# Kicker2018.net
KiCad netlist of a schematic drawn in Altium Designer
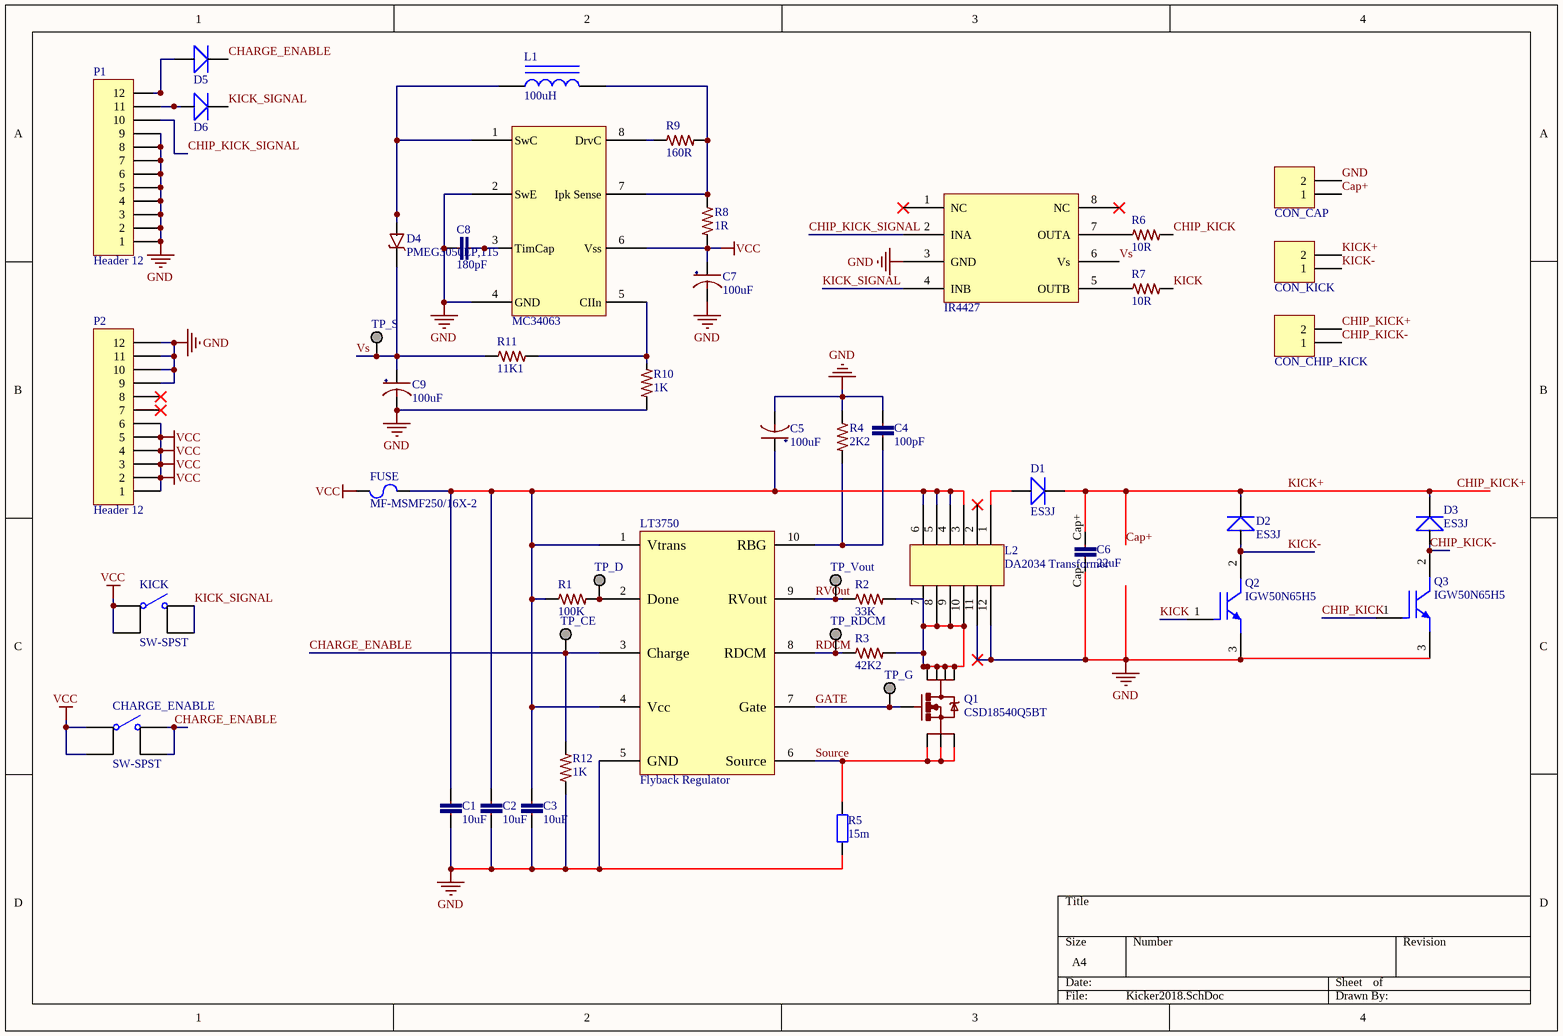
[diagram p0: Kicker2018.SchDoc]

(export (version "E")
  (design (tool "Eeschema 10.0.6"))
  (components
    (comp (ref "C1")
      (value "10uF")
      (footprint "CAPC0603(1608)55_L")
      (description "CAP CER 10UF 16V X5R 0603")
      (fields (field (name "PART NO") "EMK107BBJ106MA-T"))
      (libsource (lib "IMBEL") (part "CAPACITOR"))
    )
    (comp (ref "C2")
      (value "10uF")
      (footprint "CAPC0603(1608)55_L")
      (description "CAP CER 10UF 16V X5R 0603")
      (fields (field (name "PART NO") "EMK107BBJ106MA-T"))
      (libsource (lib "IMBEL") (part "CAPACITOR"))
    )
    (comp (ref "C3")
      (value "10uF")
      (footprint "CAPC0603(1608)55_L")
      (description "CAP CER 10UF 16V X5R 0603")
      (fields (field (name "PART NO") "EMK107BBJ106MA-T"))
      (libsource (lib "IMBEL") (part "CAPACITOR"))
    )
    (comp (ref "C4")
      (value "100pF")
      (footprint "CAPC0603(1608)55_L")
      (description "CAP CER 100PF 50V NP0 0603")
      (fields (field (name "PART NO") "GRM1885C1H101JA01D"))
      (libsource (lib "IMBEL") (part "CAPACITOR"))
    )
    (comp (ref "C5")
      (value "100uF")
      (footprint "7343-CAPPOL")
      (description "CAP TANT 100uF 25V 20% ESR = 30mOhm @ 100 kHz")
      (fields (field (name "PART NO") "T521X107M025ATE030"))
      (libsource (lib "IMBEL") (part "CT2917-100uF-1"))
    )
    (comp (ref "C6")
      (value "22uF")
      (footprint "CAP ALUM 22UF 250V")
      (libsource (lib "Schlib1") (part "CAP ALUM 22UF 250V"))
    )
    (comp (ref "C7")
      (value "100uF")
      (footprint "7343-CAPPOL")
      (description "CAP TANT 100uF 25V 20% ESR = 30mOhm @ 100 kHz")
      (fields (field (name "PART NO") "T521X107M025ATE030"))
      (libsource (lib "") (part "CT2917-100uF-1_1"))
    )
    (comp (ref "C8")
      (value "180pF")
      (footprint "0805-CAP")
      (description "CAP CER 180PF 50V NP0 0805")
      (fields (field (name "PART NO") "C0805C181K5GACTU"))
      (libsource (lib "IMBEL") (part "CC0805-180pF-2"))
    )
    (comp (ref "C9")
      (value "100uF")
      (footprint "7343-CAPPOL")
      (description "CAP TANT 100uF 25V 20% ESR = 30mOhm @ 100 kHz")
      (fields (field (name "PART NO") "T521X107M025ATE030"))
      (libsource (lib "") (part "CT2917-100uF-1_1"))
    )
    (comp (ref "CHARGE_ENABLE")
      (value "SW-SPST")
      (footprint "TACTILE SWITCH")
      (description "Single-Pole, Single-Throw Switch")
      (fields (field (name "PUBLISHER") "Altium Limited"))
      (libsource (lib "KickerSchlib") (part "SW-SPST"))
    )
    (comp (ref "CON_CAP")
      (value "OSTTA024163")
      (footprint "Term Block 2P")
      (description "2 Position Wire to Board Terminal Block Horizontal with Board 0.200\" (5.08mm) Through Hole")
      (libsource (lib "Schlib1") (part "Term Block 2P"))
    )
    (comp (ref "CON_CHIP_KICK")
      (value "OSTTA024163")
      (footprint "Term Block 2P")
      (description "2 Position Wire to Board Terminal Block Horizontal with Board 0.200\" (5.08mm) Through Hole")
      (libsource (lib "Schlib1") (part "Term Block 2P"))
    )
    (comp (ref "CON_KICK")
      (value "OSTTA024163")
      (footprint "Term Block 2P")
      (description "2 Position Wire to Board Terminal Block Horizontal with Board 0.200\" (5.08mm) Through Hole")
      (libsource (lib "Schlib1") (part "Term Block 2P"))
    )
    (comp (ref "D1") (value "ES3J") (footprint "Diode") (libsource (lib "KickerSchlib") (part "ES3J")))
    (comp (ref "D2") (value "ES3J") (footprint "Diode") (libsource (lib "KickerSchlib") (part "ES3J")))
    (comp (ref "D3") (value "ES3J") (footprint "Diode") (libsource (lib "KickerSchlib") (part "ES3J")))
    (comp (ref "D4")
      (value "PMEG3050EP,115")
      (footprint "PCBComponent")
      (description "DIODE SCHOTTKY 30V 5A SOD128")
      (libsource (lib "IMBEL") (part "PMEG3050EP,115-01.A.5"))
    )
    (comp (ref "D5")
      (value "BAS40 Diode")
      (footprint "DIODE SOD-523")
      (libsource (lib "KickerSchlib") (part "BAS40 Diode"))
    )
    (comp (ref "D6")
      (value "BAS40 Diode")
      (footprint "DIODE SOD-523")
      (libsource (lib "KickerSchlib") (part "BAS40 Diode"))
    )
    (comp (ref "FUSE")
      (value "MF-MSMF250/16X-2")
      (footprint "MF-MSMF250/16X-PCB")
      (description "PTC RESETTABLE")
      (libsource (lib "KickerSchlib") (part "MF-MSMF250/16X-2"))
    )
    (comp (ref "IR4427")
      (value "GATE DRIVER")
      (footprint "IR4427")
      (description "IC DRIVER DUAL LOW SIDE 8-SOIC")
      (libsource (lib "KickerSchlib") (part "IR4427"))
    )
    (comp (ref "KICK")
      (value "SW-SPST")
      (footprint "TACTILE SWITCH")
      (description "Single-Pole, Single-Throw Switch")
      (fields (field (name "PUBLISHER") "Altium Limited"))
      (libsource (lib "KickerSchlib") (part "SW-SPST"))
    )
    (comp (ref "L1")
      (value "100uH")
      (footprint "INDUCTOR")
      (description "Fixed Inductors 100uH 0.86A SMT")
      (libsource (lib "KickerSchlib") (part "Inductor"))
    )
    (comp (ref "L2")
      (value "DA2034 Transformer")
      (footprint "DA2034 Transformer")
      (libsource (lib "KickerSchlib") (part "DA2034 Transformer"))
    )
    (comp (ref "LT3750")
      (value "Flyback Regulator")
      (footprint "LT3750")
      (libsource (lib "KickerSchlib") (part "LT3750"))
    )
    (comp (ref "MC34063")
      (value "Switching Voltage Regulator")
      (footprint "DIP-8")
      (libsource (lib "KickerSchlib") (part "MC34063"))
    )
    (comp (ref "P1")
      (value "Header 12")
      (footprint "HDR1X12")
      (description "Header, 12-Pin")
      (fields (field (name "PUBLISHER") "Altium Limited"))
      (libsource (lib "Miscellaneous Connectors") (part "Header 12"))
    )
    (comp (ref "P2")
      (value "Header 12")
      (footprint "HDR1X12")
      (description "Header, 12-Pin")
      (fields (field (name "PUBLISHER") "Altium Limited"))
      (libsource (lib "Miscellaneous Connectors") (part "Header 12"))
    )
    (comp (ref "Q1")
      (value "CSD18540Q5BT")
      (footprint "PCBComponent")
      (description "MOSFET N-CH 60V 100A 8VSON")
      (libsource (lib "IMBEL") (part "MOSFET-NCHANNEL"))
    )
    (comp (ref "Q2")
      (value "IGW50N65H5")
      (footprint "INF-PG-TO247-3-44")
      (description "650 V IGBT High Speed Switching Series Fifth Generation, 80 A IC, PG-TO247-3-44, Tube, Green")
      (fields (field (name "MANUFACTURER") "Infineon"))
      (libsource (lib "KickerSchlib") (part "IGW50N65H5"))
    )
    (comp (ref "Q3")
      (value "IGW50N65H5")
      (footprint "INF-PG-TO247-3-44")
      (description "650 V IGBT High Speed Switching Series Fifth Generation, 80 A IC, PG-TO247-3-44, Tube, Green")
      (fields (field (name "MANUFACTURER") "Infineon"))
      (libsource (lib "KickerSchlib") (part "IGW50N65H5"))
    )
    (comp (ref "R1")
      (value "100K")
      (footprint "0402-RES-HD")
      (description "RES 100K OHM 1/10W 1% 0402 SMD 1")
      (fields (field (name "PART NO") "ERJ-2GEJ104X"))
      (libsource (lib "IMBEL") (part "RESISTOR"))
    )
    (comp (ref "R2")
      (value "33K")
      (footprint "0402-RES-HD")
      (description "RES 33K OHM 1/10W 1% 0402 SMD")
      (fields (field (name "PART NO") "ERJ-2RKF3302X"))
      (libsource (lib "IMBEL") (part "RESISTOR"))
    )
    (comp (ref "R3")
      (value "42K2")
      (footprint "0402-RES-HD")
      (description "RES 42.2K OHM 1/10W 1% 0402 SMD")
      (fields (field (name "PART NO") "ERJ-2RKF4222X"))
      (libsource (lib "Schlib1") (part "RESISTOR"))
    )
    (comp (ref "R4")
      (value "2K2")
      (footprint "0402-RES-HD")
      (description "RES 2.2K OHM 1/10W 1% 0402 SMD")
      (fields (field (name "PART NO") "ERJ-2RKF2201X"))
      (libsource (lib "IMBEL") (part "RESISTOR"))
    )
    (comp (ref "R5")
      (value "15m")
      (footprint "RES1206")
      (description "Resistor")
      (fields (field (name "PUBLISHER") "Altium Limited"))
      (libsource (lib "Schlib1") (part "Res2"))
    )
    (comp (ref "R6")
      (value "10R")
      (footprint "0402-RES-HD")
      (description "RES 10 OHM 1/10W 1% 0402 SMD")
      (fields (field (name "PART NO") "ERJ-2RKF10R0X"))
      (libsource (lib "IMBEL") (part "RESISTOR"))
    )
    (comp (ref "R7")
      (value "10R")
      (footprint "0402-RES-HD")
      (description "RES 10 OHM 1/10W 1% 0402 SMD")
      (fields (field (name "PART NO") "ERJ-2RKF10R0X"))
      (libsource (lib "IMBEL") (part "RESISTOR"))
    )
    (comp (ref "R8")
      (value "1R")
      (footprint "0805-RES")
      (description "RES SMD 1 OHM 1% 1/8W 0805")
      (fields (field (name "PART NO") "CRCW08051R00FKEA"))
      (libsource (lib "IMBEL") (part "R0805-1R-1%-1"))
    )
    (comp (ref "R9")
      (value "160R")
      (footprint "0805-RES")
      (description "RES 160 OHM 1/8W .5% 0805 SMD")
      (fields (field (name "PART NO") "ERA-6AED161V"))
      (libsource (lib "IMBEL") (part "R0805-160R-5"))
    )
    (comp (ref "R10")
      (value "1K")
      (footprint "0402-RES-HD")
      (description "RES 1K OHM 1/10W 1% 0402 SMD")
      (fields (field (name "PART NO") "ERJ-2RKF1001X"))
      (libsource (lib "IMBEL") (part "R0402-1K-A.9"))
    )
    (comp (ref "R11")
      (value "11K1")
      (footprint "0402-RES-HD")
      (description "RES 11.1 KOHM 1/16W 0.1% 0402 SMD")
      (fields (field (name "PART NO") "TNPW040211K1BEED"))
      (libsource (lib "IMBEL") (part "R0402-11K1-1"))
    )
    (comp (ref "R12")
      (value "1K")
      (footprint "0402-RES-HD")
      (description "RES 1K OHM 1/10W 1% 0402 SMD")
      (fields (field (name "PART NO") "ERJ-2RKF1001X"))
      (libsource (lib "IMBEL") (part "RESISTOR"))
    )
    (comp (ref "TP_CE")
      (value "~")
      (footprint "TP-PCB")
      (description "TESTPOINT")
      (libsource (lib "IMBEL") (part "TP-SCH"))
    )
    (comp (ref "TP_D")
      (value "~")
      (footprint "TP-PCB")
      (description "TESTPOINT")
      (libsource (lib "IMBEL") (part "TP-SCH"))
    )
    (comp (ref "TP_G")
      (value "~")
      (footprint "TP-PCB")
      (description "TESTPOINT")
      (libsource (lib "IMBEL") (part "TP-SCH"))
    )
    (comp (ref "TP_RDCM")
      (value "~")
      (footprint "TP-PCB")
      (description "TESTPOINT")
      (libsource (lib "IMBEL") (part "TP-SCH"))
    )
    (comp (ref "TP_S")
      (value "~")
      (footprint "TP-PCB")
      (description "TESTPOINT")
      (libsource (lib "IMBEL") (part "TP-SCH"))
    )
    (comp (ref "TP_Vout")
      (value "~")
      (footprint "TP-PCB")
      (description "TESTPOINT")
      (libsource (lib "IMBEL") (part "TP-SCH"))
    )
  )
  (nets
    (net (code "1") (name "/CHARGE_ENABLE") (class "Default")
      (node (ref "CHARGE_ENABLE") (pin "3") (pinfunction "3_3") (pintype "passive"))
      (node (ref "CHARGE_ENABLE") (pin "4") (pinfunction "4_4") (pintype "passive"))
      (node (ref "D5") (pin "2") (pinfunction "D-_2") (pintype "passive"))
      (node (ref "LT3750") (pin "3") (pinfunction "Charge_3") (pintype "passive"))
      (node (ref "R12") (pin "2") (pinfunction "2_2") (pintype "passive"))
      (node (ref "TP_CE") (pin "1") (pinfunction "1_1") (pintype "passive"))
    )
    (net (code "2") (name "/CHIP_KICK") (class "Default")
      (node (ref "Q3") (pin "1") (pinfunction "G_1") (pintype "passive"))
      (node (ref "R6") (pin "2") (pinfunction "2_2") (pintype "passive"))
    )
    (net (code "3") (name "/CHIP_KICK+") (class "Default")
      (node (ref "C6") (pin "Cap+") (pinfunction "Cap+_Cap+") (pintype "passive"))
      (node (ref "CON_CAP") (pin "1") (pinfunction "1_1") (pintype "passive"))
      (node (ref "CON_CHIP_KICK") (pin "2") (pinfunction "2_2") (pintype "passive"))
      (node (ref "CON_KICK") (pin "2") (pinfunction "2_2") (pintype "passive"))
      (node (ref "D1") (pin "D1+") (pinfunction "D1+_D1+") (pintype "passive"))
      (node (ref "D2") (pin "D1+") (pinfunction "D1+_D1+") (pintype "passive"))
      (node (ref "D3") (pin "D1+") (pinfunction "D1+_D1+") (pintype "passive"))
    )
    (net (code "4") (name "/CHIP_KICK-") (class "Default")
      (node (ref "CON_CHIP_KICK") (pin "1") (pinfunction "1_1") (pintype "passive"))
      (node (ref "D3") (pin "D1-") (pinfunction "D1-_D1-") (pintype "passive"))
      (node (ref "Q3") (pin "2") (pinfunction "C_2") (pintype "passive"))
    )
    (net (code "5") (name "/CHIP_KICK_SIGNAL") (class "Default")
      (node (ref "IR4427") (pin "2") (pinfunction "INA_2") (pintype "passive"))
      (node (ref "P1") (pin "10") (pinfunction "10_10") (pintype "passive"))
    )
    (net (code "6") (name "/GATE") (class "Default")
      (node (ref "LT3750") (pin "7") (pinfunction "Gate_7") (pintype "passive"))
      (node (ref "Q1") (pin "4") (pinfunction "G_4") (pintype "passive"))
      (node (ref "TP_G") (pin "1") (pinfunction "1_1") (pintype "passive"))
    )
    (net (code "7") (name "/KICK") (class "Default")
      (node (ref "Q2") (pin "1") (pinfunction "G_1") (pintype "passive"))
      (node (ref "R7") (pin "2") (pinfunction "2_2") (pintype "passive"))
    )
    (net (code "8") (name "/KICK-") (class "Default")
      (node (ref "CON_KICK") (pin "1") (pinfunction "1_1") (pintype "passive"))
      (node (ref "D2") (pin "D1-") (pinfunction "D1-_D1-") (pintype "passive"))
      (node (ref "Q2") (pin "2") (pinfunction "C_2") (pintype "passive"))
    )
    (net (code "9") (name "/KICK_SIGNAL") (class "Default")
      (node (ref "D6") (pin "2") (pinfunction "D-_2") (pintype "passive"))
      (node (ref "IR4427") (pin "4") (pinfunction "INB_4") (pintype "passive"))
      (node (ref "KICK") (pin "3") (pinfunction "3_3") (pintype "passive"))
      (node (ref "KICK") (pin "4") (pinfunction "4_4") (pintype "passive"))
    )
    (net (code "10") (name "/RDCM") (class "Default")
      (node (ref "LT3750") (pin "8") (pinfunction "RDCM_8") (pintype "passive"))
      (node (ref "R3") (pin "1") (pinfunction "1_1") (pintype "passive"))
      (node (ref "TP_RDCM") (pin "1") (pinfunction "1_1") (pintype "passive"))
    )
    (net (code "11") (name "/RVOut") (class "Default")
      (node (ref "LT3750") (pin "9") (pinfunction "RVout_9") (pintype "passive"))
      (node (ref "R2") (pin "1") (pinfunction "1_1") (pintype "passive"))
      (node (ref "TP_Vout") (pin "1") (pinfunction "1_1") (pintype "passive"))
    )
    (net (code "12") (name "/Source") (class "Default")
      (node (ref "LT3750") (pin "6") (pinfunction "Source_6") (pintype "passive"))
      (node (ref "Q1") (pin "1") (pinfunction "S_1") (pintype "passive"))
      (node (ref "Q1") (pin "2") (pinfunction "S_2") (pintype "passive"))
      (node (ref "Q1") (pin "3") (pinfunction "S_3") (pintype "passive"))
      (node (ref "R5") (pin "1") (pinfunction "1_1") (pintype "passive"))
    )
    (net (code "13") (name "/Vs") (class "Default")
      (node (ref "C9") (pin "1") (pinfunction "+_1") (pintype "passive"))
      (node (ref "D4") (pin "1") (pinfunction "C_1") (pintype "passive"))
      (node (ref "IR4427") (pin "6") (pinfunction "Vs_6") (pintype "passive"))
      (node (ref "R11") (pin "1") (pinfunction "1_1") (pintype "passive"))
      (node (ref "TP_S") (pin "1") (pinfunction "1_1") (pintype "passive"))
    )
    (net (code "14") (name "GND") (class "Default")
      (node (ref "C1") (pin "2") (pinfunction "2_2") (pintype "passive"))
      (node (ref "C2") (pin "2") (pinfunction "2_2") (pintype "passive"))
      (node (ref "C3") (pin "2") (pinfunction "2_2") (pintype "passive"))
      (node (ref "C4") (pin "1") (pinfunction "1_1") (pintype "passive"))
      (node (ref "C5") (pin "2") (pinfunction "-_2") (pintype "passive"))
      (node (ref "C6") (pin "Cap-") (pinfunction "Cap-_Cap-") (pintype "passive"))
      (node (ref "C7") (pin "2") (pinfunction "-_2") (pintype "passive"))
      (node (ref "C8") (pin "1") (pinfunction "1_1") (pintype "passive"))
      (node (ref "C9") (pin "2") (pinfunction "-_2") (pintype "passive"))
      (node (ref "CON_CAP") (pin "2") (pinfunction "2_2") (pintype "passive"))
      (node (ref "IR4427") (pin "3") (pinfunction "GND_3") (pintype "passive"))
      (node (ref "L2") (pin "11") (pinfunction "11_11") (pintype "passive"))
      (node (ref "L2") (pin "12") (pinfunction "12_12") (pintype "passive"))
      (node (ref "LT3750") (pin "5") (pinfunction "GND_5") (pintype "passive"))
      (node (ref "MC34063") (pin "2") (pinfunction "SwE_2") (pintype "passive"))
      (node (ref "MC34063") (pin "4") (pinfunction "GND_4") (pintype "passive"))
      (node (ref "P1") (pin "1") (pinfunction "1_1") (pintype "passive"))
      (node (ref "P1") (pin "2") (pinfunction "2_2") (pintype "passive"))
      (node (ref "P1") (pin "3") (pinfunction "3_3") (pintype "passive"))
      (node (ref "P1") (pin "4") (pinfunction "4_4") (pintype "passive"))
      (node (ref "P1") (pin "5") (pinfunction "5_5") (pintype "passive"))
      (node (ref "P1") (pin "6") (pinfunction "6_6") (pintype "passive"))
      (node (ref "P1") (pin "7") (pinfunction "7_7") (pintype "passive"))
      (node (ref "P1") (pin "8") (pinfunction "8_8") (pintype "passive"))
      (node (ref "P1") (pin "9") (pinfunction "9_9") (pintype "passive"))
      (node (ref "P2") (pin "10") (pinfunction "10_10") (pintype "passive"))
      (node (ref "P2") (pin "11") (pinfunction "11_11") (pintype "passive"))
      (node (ref "P2") (pin "12") (pinfunction "12_12") (pintype "passive"))
      (node (ref "P2") (pin "9") (pinfunction "9_9") (pintype "passive"))
      (node (ref "Q2") (pin "3") (pinfunction "E_3") (pintype "passive"))
      (node (ref "Q3") (pin "3") (pinfunction "E_3") (pintype "passive"))
      (node (ref "R10") (pin "1") (pinfunction "1_1") (pintype "passive"))
      (node (ref "R12") (pin "1") (pinfunction "1_1") (pintype "passive"))
      (node (ref "R4") (pin "2") (pinfunction "2_2") (pintype "passive"))
      (node (ref "R5") (pin "2") (pinfunction "2_2") (pintype "passive"))
    )
    (net (code "15") (name "Net-(C5-+)") (class "Default")
      (node (ref "C1") (pin "1") (pinfunction "1_1") (pintype "passive"))
      (node (ref "C2") (pin "1") (pinfunction "1_1") (pintype "passive"))
      (node (ref "C3") (pin "1") (pinfunction "1_1") (pintype "passive"))
      (node (ref "C5") (pin "1") (pinfunction "+_1") (pintype "passive"))
      (node (ref "FUSE") (pin "2") (pinfunction "2_2") (pintype "passive"))
      (node (ref "L2") (pin "3") (pinfunction "3_3") (pintype "passive"))
      (node (ref "L2") (pin "4") (pinfunction "4_4") (pintype "passive"))
      (node (ref "L2") (pin "5") (pinfunction "5_5") (pintype "passive"))
      (node (ref "L2") (pin "6") (pinfunction "6_6") (pintype "passive"))
      (node (ref "LT3750") (pin "1") (pinfunction "Vtrans_1") (pintype "passive"))
      (node (ref "LT3750") (pin "4") (pinfunction "Vcc_4") (pintype "passive"))
      (node (ref "R1") (pin "1") (pinfunction "1_1") (pintype "passive"))
    )
    (net (code "16") (name "Net-(D1-PadD1-)") (class "Default")
      (node (ref "D1") (pin "D1-") (pinfunction "D1-_D1-") (pintype "passive"))
      (node (ref "L2") (pin "1") (pinfunction "1_1") (pintype "passive"))
    )
    (net (code "17") (name "Net-(D4-A)") (class "Default")
      (node (ref "D4") (pin "2") (pinfunction "A_2") (pintype "passive"))
      (node (ref "L1") (pin "1") (pinfunction "1_1") (pintype "passive"))
      (node (ref "MC34063") (pin "1") (pinfunction "SwC_1") (pintype "passive"))
    )
    (net (code "18") (name "Net-(D5-D+)") (class "Default")
      (node (ref "D5") (pin "1") (pinfunction "D+_1") (pintype "passive"))
      (node (ref "P1") (pin "12") (pinfunction "12_12") (pintype "passive"))
    )
    (net (code "19") (name "Net-(D6-D+)") (class "Default")
      (node (ref "D6") (pin "1") (pinfunction "D+_1") (pintype "passive"))
      (node (ref "P1") (pin "11") (pinfunction "11_11") (pintype "passive"))
    )
    (net (code "20") (name "Net-(IR4427-OUTA)") (class "Default")
      (node (ref "IR4427") (pin "7") (pinfunction "OUTA_7") (pintype "passive"))
      (node (ref "R6") (pin "1") (pinfunction "1_1") (pintype "passive"))
    )
    (net (code "21") (name "Net-(IR4427-OUTB)") (class "Default")
      (node (ref "IR4427") (pin "5") (pinfunction "OUTB_5") (pintype "passive"))
      (node (ref "R7") (pin "1") (pinfunction "1_1") (pintype "passive"))
    )
    (net (code "22") (name "Net-(L2-Pad10)") (class "Default")
      (node (ref "L2") (pin "10") (pinfunction "10_10") (pintype "passive"))
      (node (ref "L2") (pin "7") (pinfunction "7_7") (pintype "passive"))
      (node (ref "L2") (pin "8") (pinfunction "8_8") (pintype "passive"))
      (node (ref "L2") (pin "9") (pinfunction "9_9") (pintype "passive"))
      (node (ref "Q1") (pin "5") (pinfunction "D_5") (pintype "passive"))
      (node (ref "Q1") (pin "6") (pinfunction "D_6") (pintype "passive"))
      (node (ref "Q1") (pin "7") (pinfunction "D_7") (pintype "passive"))
      (node (ref "Q1") (pin "8") (pinfunction "D_8") (pintype "passive"))
      (node (ref "R2") (pin "2") (pinfunction "2_2") (pintype "passive"))
      (node (ref "R3") (pin "2") (pinfunction "2_2") (pintype "passive"))
    )
    (net (code "23") (name "Net-(LT3750-Done)") (class "Default")
      (node (ref "LT3750") (pin "2") (pinfunction "Done_2") (pintype "passive"))
      (node (ref "R1") (pin "2") (pinfunction "2_2") (pintype "passive"))
      (node (ref "TP_D") (pin "1") (pinfunction "1_1") (pintype "passive"))
    )
    (net (code "24") (name "Net-(LT3750-RBG)") (class "Default")
      (node (ref "C4") (pin "2") (pinfunction "2_2") (pintype "passive"))
      (node (ref "LT3750") (pin "10") (pinfunction "RBG_10") (pintype "passive"))
      (node (ref "R4") (pin "1") (pinfunction "1_1") (pintype "passive"))
    )
    (net (code "25") (name "Net-(MC34063-CIIn)") (class "Default")
      (node (ref "MC34063") (pin "5") (pinfunction "CIIn_5") (pintype "passive"))
      (node (ref "R10") (pin "2") (pinfunction "2_2") (pintype "passive"))
      (node (ref "R11") (pin "2") (pinfunction "2_2") (pintype "passive"))
    )
    (net (code "26") (name "Net-(MC34063-DrvC)") (class "Default")
      (node (ref "MC34063") (pin "8") (pinfunction "DrvC_8") (pintype "passive"))
      (node (ref "R9") (pin "1") (pinfunction "1_1") (pintype "passive"))
    )
    (net (code "27") (name "Net-(MC34063-Ipk_Sense)") (class "Default")
      (node (ref "L1") (pin "2") (pinfunction "2_2") (pintype "passive"))
      (node (ref "MC34063") (pin "7") (pinfunction "Ipk_Sense_7") (pintype "passive"))
      (node (ref "R8") (pin "2") (pinfunction "2_2") (pintype "passive"))
      (node (ref "R9") (pin "2") (pinfunction "2_2") (pintype "passive"))
    )
    (net (code "28") (name "Net-(MC34063-TimCap)") (class "Default")
      (node (ref "C8") (pin "2") (pinfunction "2_2") (pintype "passive"))
      (node (ref "MC34063") (pin "3") (pinfunction "TimCap_3") (pintype "passive"))
    )
    (net (code "29") (name "VCC") (class "Default")
      (node (ref "C7") (pin "1") (pinfunction "+_1") (pintype "passive"))
      (node (ref "CHARGE_ENABLE") (pin "1") (pinfunction "1_1") (pintype "passive"))
      (node (ref "CHARGE_ENABLE") (pin "2") (pinfunction "2_2") (pintype "passive"))
      (node (ref "FUSE") (pin "1") (pinfunction "1_1") (pintype "passive"))
      (node (ref "KICK") (pin "1") (pinfunction "1_1") (pintype "passive"))
      (node (ref "KICK") (pin "2") (pinfunction "2_2") (pintype "passive"))
      (node (ref "MC34063") (pin "6") (pinfunction "Vss_6") (pintype "passive"))
      (node (ref "P2") (pin "1") (pinfunction "1_1") (pintype "passive"))
      (node (ref "P2") (pin "2") (pinfunction "2_2") (pintype "passive"))
      (node (ref "P2") (pin "3") (pinfunction "3_3") (pintype "passive"))
      (node (ref "P2") (pin "4") (pinfunction "4_4") (pintype "passive"))
      (node (ref "P2") (pin "5") (pinfunction "5_5") (pintype "passive"))
      (node (ref "P2") (pin "6") (pinfunction "6_6") (pintype "passive"))
      (node (ref "R8") (pin "1") (pinfunction "1_1") (pintype "passive"))
    )
    (net (code "30") (name "unconnected-(IR4427-NC-Pad1)") (class "Default")
      (node (ref "IR4427") (pin "1") (pinfunction "NC_1") (pintype "passive+no_connect"))
    )
    (net (code "31") (name "unconnected-(IR4427-NC-Pad8)") (class "Default")
      (node (ref "IR4427") (pin "8") (pinfunction "NC_8") (pintype "passive+no_connect"))
    )
    (net (code "32") (name "unconnected-(L2-Pad2)") (class "Default")
      (node (ref "L2") (pin "2") (pinfunction "2_2") (pintype "passive+no_connect"))
    )
    (net (code "33") (name "unconnected-(P2-Pad7)") (class "Default")
      (node (ref "P2") (pin "7") (pinfunction "7_7") (pintype "passive+no_connect"))
    )
    (net (code "34") (name "unconnected-(P2-Pad8)") (class "Default")
      (node (ref "P2") (pin "8") (pinfunction "8_8") (pintype "passive+no_connect"))
    )
  )
)
